# PowerDelivery.net
KiCad netlist of a schematic drawn in Altium Designer
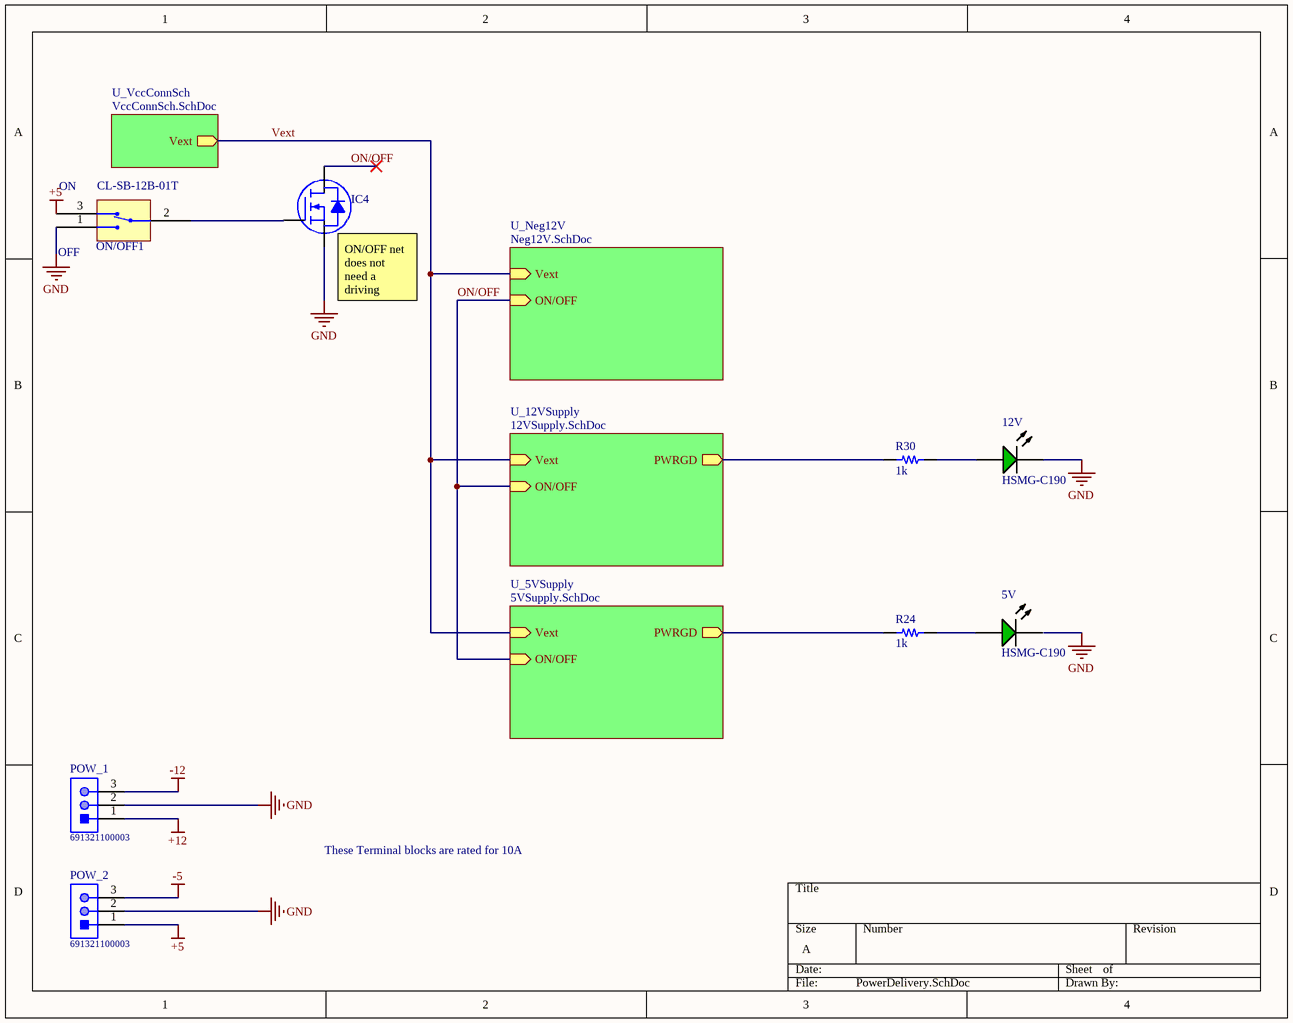
[diagram p0: PowerDelivery.SchDoc]

(export (version "E")
  (design (tool "Eeschema 10.0.6"))
  (components
    (comp (ref "5V")
      (value "HSMG-C190")
      (footprint "AVAG-HSMX-C190_V")
      (description "Chip LED, Green, 2.2 V, -40 to 85 degC, 2-Pin SMD, RoHS, Tape and Reel")
      (libsource (lib "Altium Content Vault") (part "LED-GREEN-AK-2"))
    )
    (comp (ref "12V")
      (value "HSMG-C190")
      (footprint "AVAG-HSMX-C190_V")
      (description "Chip LED, Green, 2.2 V, -40 to 85 degC, 2-Pin SMD, RoHS, Tape and Reel")
      (libsource (lib "Altium Content Vault") (part "LED-GREEN-AK-2"))
    )
    (comp (ref "IC4")
      (value "BSS138WH6327XTSA1")
      (footprint "INFINEON SOT-323-3")
      (description "MOSFET N-CH 60V 280MA SOT-323")
      (fields (field (name "MANUFACTURER") "Infineon Technologies"))
      (libsource (lib "Celestial Library Database") (part "INFINEON MOSFET N-CH SOT-23-3"))
    )
    (comp (ref "ON/OFF1")
      (value "CL-SB-12B-01T")
      (footprint "SW_CL-SB-12B-01")
      (description "SWITCH SLIDE SPDT 200MA 12V")
      (fields (field (name "MANUFACTURER") "Nidec Copal Electronics"))
      (libsource (lib "Celestial Library Database") (part "CL-SB-12B-01T"))
    )
    (comp (ref "POW_1")
      (value "691321100003")
      (footprint "691321100003")
      (description "Serie 3211 - 3.50mm Vertical PCB Header WR-TBL, 3 pin")
      (fields (field (name "MANUFACTURER") "Wurth Elektronik") (field (name "PUBLISHER") "WurthElektronik"))
      (libsource (lib "Altium Content Vault") (part "WE-CN-1P-M-R3"))
    )
    (comp (ref "POW_2")
      (value "691321100003")
      (footprint "691321100003")
      (description "Serie 3211 - 3.50mm Vertical PCB Header WR-TBL, 3 pin")
      (fields (field (name "MANUFACTURER") "Wurth Elektronik") (field (name "PUBLISHER") "WurthElektronik"))
      (libsource (lib "Altium Content Vault") (part "WE-CN-1P-M-R3"))
    )
    (comp (ref "R24")
      (value "1k")
      (footprint "RES 1206/3216")
      (description "RES SMD 1K OHM 1% 1/4W 1206")
      (fields
        (field (name "PART NUMBER") "ERJ-8ENF1001V")
        (field (name "MANUFACTURER") "Panasonic Electronic Components")
      )
      (libsource (lib "Celestial Library Database") (part "Resistor"))
    )
    (comp (ref "R30")
      (value "1k")
      (footprint "RES 1206/3216")
      (description "RES SMD 1K OHM 1% 1/4W 1206")
      (fields
        (field (name "PART NUMBER") "ERJ-8ENF1001V")
        (field (name "MANUFACTURER") "Panasonic Electronic Components")
      )
      (libsource (lib "Celestial Library Database") (part "Resistor"))
    )
  )
  (nets
    (net (code "1") (name "+5") (class "Default")
      (node (ref "ON/OFF1") (pin "3") (pinfunction "GND_3") (pintype "passive"))
      (node (ref "POW_2") (pin "1") (pinfunction "1_1") (pintype "passive"))
    )
    (net (code "2") (name "+12") (class "Default")
      (node (ref "POW_1") (pin "1") (pinfunction "1_1") (pintype "passive"))
    )
    (net (code "3") (name "-5") (class "Default")
      (node (ref "POW_2") (pin "3") (pinfunction "3_3") (pintype "passive"))
    )
    (net (code "4") (name "-12") (class "Default")
      (node (ref "POW_1") (pin "3") (pinfunction "3_3") (pintype "passive"))
    )
    (net (code "5") (name "/ON{slash}OFF") (class "Default")
      (node (ref "IC4") (pin "2") (pinfunction "D_2") (pintype "passive+no_connect"))
    )
    (net (code "6") (name "/PWRGD") (class "Default")
      (node (ref "R24") (pin "2") (pinfunction "2_2") (pintype "passive"))
    )
    (net (code "7") (name "/PWRGD_1") (class "Default")
      (node (ref "R30") (pin "2") (pinfunction "2_2") (pintype "passive"))
    )
    (net (code "9") (name "GND") (class "Default")
      (node (ref "12V") (pin "2") (pinfunction "K_2") (pintype "passive"))
      (node (ref "IC4") (pin "3") (pinfunction "S_3") (pintype "passive"))
      (node (ref "ON/OFF1") (pin "1") (pinfunction "GND_1") (pintype "passive"))
      (node (ref "POW_1") (pin "2") (pinfunction "2_2") (pintype "passive"))
      (node (ref "POW_2") (pin "2") (pinfunction "2_2") (pintype "passive"))
    )
    (net (code "10") (name "Net-(5V-A)") (class "Default")
      (node (ref "5V") (pin "1") (pinfunction "A_1") (pintype "passive"))
      (node (ref "R24") (pin "1") (pinfunction "1_1") (pintype "passive"))
    )
    (net (code "11") (name "Net-(12V-A)") (class "Default")
      (node (ref "12V") (pin "1") (pinfunction "A_1") (pintype "passive"))
      (node (ref "R30") (pin "1") (pinfunction "1_1") (pintype "passive"))
    )
    (net (code "12") (name "Net-(IC4-G)") (class "Default")
      (node (ref "IC4") (pin "1") (pinfunction "G_1") (pintype "passive"))
      (node (ref "ON/OFF1") (pin "2") (pinfunction "GND_2") (pintype "passive"))
    )
    (net (code "13") (name "unconnected-(5V-K-Pad2)") (class "Default")
      (node (ref "5V") (pin "2") (pinfunction "K_2") (pintype "passive"))
    )
  )
)
